# Altium_Schematic_CO2_Sensor_Rev1.net
KiCad netlist of a schematic drawn in Altium Designer
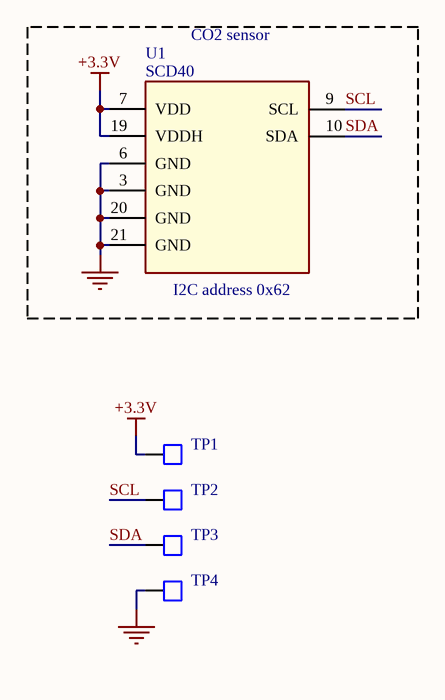
[diagram p0: Altium_Schematic_CO2_Sensor_Rev1.SchDoc]

(export (version "E")
  (design (tool "Eeschema 10.0.6"))
  (components
    (comp (ref "TP1")
      (value "Test Point, 1mm Top Layer")
      (footprint "TP100TL")
      (libsource (lib "MAR") (part "Test Point, 1mm Top Layer"))
    )
    (comp (ref "TP2")
      (value "Test Point, 1mm Top Layer")
      (footprint "TP100TL")
      (libsource (lib "MAR") (part "Test Point, 1mm Top Layer"))
    )
    (comp (ref "TP3")
      (value "Test Point, 1mm Top Layer")
      (footprint "TP100TL")
      (libsource (lib "MAR") (part "Test Point, 1mm Top Layer"))
    )
    (comp (ref "TP4")
      (value "Test Point, 1mm Top Layer")
      (footprint "TP100TL")
      (libsource (lib "MAR") (part "Test Point, 1mm Top Layer"))
    )
    (comp (ref "U1")
      (value "SCD40")
      (footprint "SCD40")
      (description "CO2 SENSOR 50 PPM I2C SMD")
      (fields (field (name "MANUFACTURER") "Sensirion"))
      (libsource (lib "MAR") (part "SCD40"))
    )
  )
  (nets
    (net (code "1") (name "+3.3V") (class "Default")
      (node (ref "TP1") (pin "1") (pinfunction "1_1") (pintype "passive"))
      (node (ref "U1") (pin "19") (pinfunction "VDDH_19") (pintype "power_in"))
      (node (ref "U1") (pin "7") (pinfunction "VDD_7") (pintype "power_in"))
    )
    (net (code "2") (name "/SCL") (class "Default")
      (node (ref "TP2") (pin "1") (pinfunction "1_1") (pintype "passive"))
      (node (ref "U1") (pin "9") (pinfunction "SCL_9") (pintype "passive"))
    )
    (net (code "3") (name "/SDA") (class "Default")
      (node (ref "TP3") (pin "1") (pinfunction "1_1") (pintype "passive"))
      (node (ref "U1") (pin "10") (pinfunction "SDA_10") (pintype "passive"))
    )
    (net (code "4") (name "GND") (class "Default")
      (node (ref "TP4") (pin "1") (pinfunction "1_1") (pintype "passive"))
      (node (ref "U1") (pin "20") (pinfunction "GND_20") (pintype "power_in"))
      (node (ref "U1") (pin "21") (pinfunction "GND_21") (pintype "power_in"))
      (node (ref "U1") (pin "3") (pinfunction "GND_3") (pintype "power_in"))
      (node (ref "U1") (pin "6") (pinfunction "GND_6") (pintype "power_in"))
    )
  )
)
